# untitled.net
KiCad netlist of a schematic drawn in EAGLE
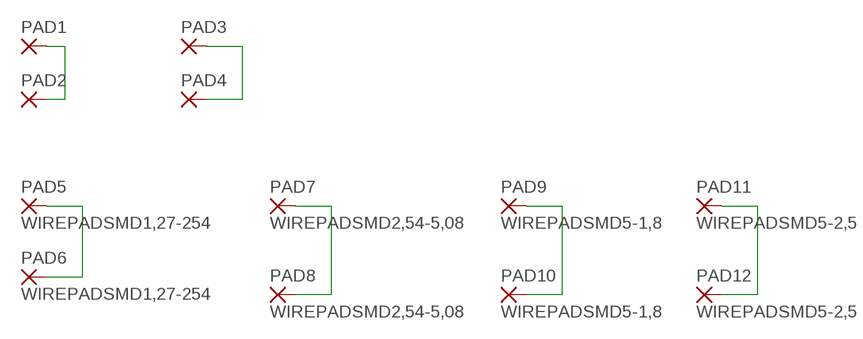
[diagram p0: schematic, sheet 1]

(export (version "E")
  (design (tool "Eeschema 10.0.6"))
  (components
    (comp (ref "PAD1")
      (value "SMD2")
      (footprint "eagle-import:SMD1,27-2,54")
      (libsource (lib "eagle-import") (part "SMD2"))
    )
    (comp (ref "PAD2")
      (value "SMD2")
      (footprint "eagle-import:SMD1,27-2,54")
      (libsource (lib "eagle-import") (part "SMD2"))
    )
    (comp (ref "PAD3")
      (value "SMD5")
      (footprint "eagle-import:SMD2,54-5,08")
      (libsource (lib "eagle-import") (part "SMD5"))
    )
    (comp (ref "PAD4")
      (value "SMD5")
      (footprint "eagle-import:SMD2,54-5,08")
      (libsource (lib "eagle-import") (part "SMD5"))
    )
    (comp (ref "PAD5")
      (value "WIREPADSMD1,27-254")
      (footprint "eagle-import:SMD1,27-2,54")
      (libsource (lib "eagle-import") (part "WIREPADSMD1,27-254"))
    )
    (comp (ref "PAD6")
      (value "WIREPADSMD1,27-254")
      (footprint "eagle-import:SMD1,27-2,54")
      (libsource (lib "eagle-import") (part "WIREPADSMD1,27-254"))
    )
    (comp (ref "PAD7")
      (value "WIREPADSMD2,54-5,08")
      (footprint "eagle-import:SMD2,54-5,08")
      (libsource (lib "eagle-import") (part "WIREPADSMD2,54-5,08"))
    )
    (comp (ref "PAD8")
      (value "WIREPADSMD2,54-5,08")
      (footprint "eagle-import:SMD2,54-5,08")
      (libsource (lib "eagle-import") (part "WIREPADSMD2,54-5,08"))
    )
    (comp (ref "PAD9")
      (value "WIREPADSMD5-1,8")
      (footprint "eagle-import:5-1,8")
      (libsource (lib "eagle-import") (part "WIREPADSMD5-1,8"))
    )
    (comp (ref "PAD10")
      (value "WIREPADSMD5-1,8")
      (footprint "eagle-import:5-1,8")
      (libsource (lib "eagle-import") (part "WIREPADSMD5-1,8"))
    )
    (comp (ref "PAD11")
      (value "WIREPADSMD5-2,5")
      (footprint "eagle-import:5-2,5")
      (libsource (lib "eagle-import") (part "WIREPADSMD5-2,5"))
    )
    (comp (ref "PAD12")
      (value "WIREPADSMD5-2,5")
      (footprint "eagle-import:5-2,5")
      (libsource (lib "eagle-import") (part "WIREPADSMD5-2,5"))
    )
  )
  (nets
    (net (code "1") (name "Net-(PAD1-P)") (class "Default")
      (node (ref "PAD1") (pin "1") (pinfunction "P_1") (pintype "passive"))
      (node (ref "PAD2") (pin "1") (pinfunction "P_1") (pintype "passive"))
    )
    (net (code "2") (name "Net-(PAD3-P)") (class "Default")
      (node (ref "PAD3") (pin "1") (pinfunction "P_1") (pintype "passive"))
      (node (ref "PAD4") (pin "1") (pinfunction "P_1") (pintype "passive"))
    )
    (net (code "3") (name "Net-(PAD5-P)") (class "Default")
      (node (ref "PAD5") (pin "1") (pinfunction "P_1") (pintype "passive"))
      (node (ref "PAD6") (pin "1") (pinfunction "P_1") (pintype "passive"))
    )
    (net (code "4") (name "Net-(PAD7-P)") (class "Default")
      (node (ref "PAD7") (pin "1") (pinfunction "P_1") (pintype "passive"))
      (node (ref "PAD8") (pin "1") (pinfunction "P_1") (pintype "passive"))
    )
    (net (code "5") (name "Net-(PAD10-P)") (class "Default")
      (node (ref "PAD10") (pin "1") (pinfunction "P_1") (pintype "passive"))
      (node (ref "PAD9") (pin "1") (pinfunction "P_1") (pintype "passive"))
    )
    (net (code "6") (name "Net-(PAD11-P)") (class "Default")
      (node (ref "PAD11") (pin "1") (pinfunction "P_1") (pintype "passive"))
      (node (ref "PAD12") (pin "1") (pinfunction "P_1") (pintype "passive"))
    )
  )
)
